# 27-JTAG_BUFFER.net
KiCad netlist of a schematic drawn in Altium Designer
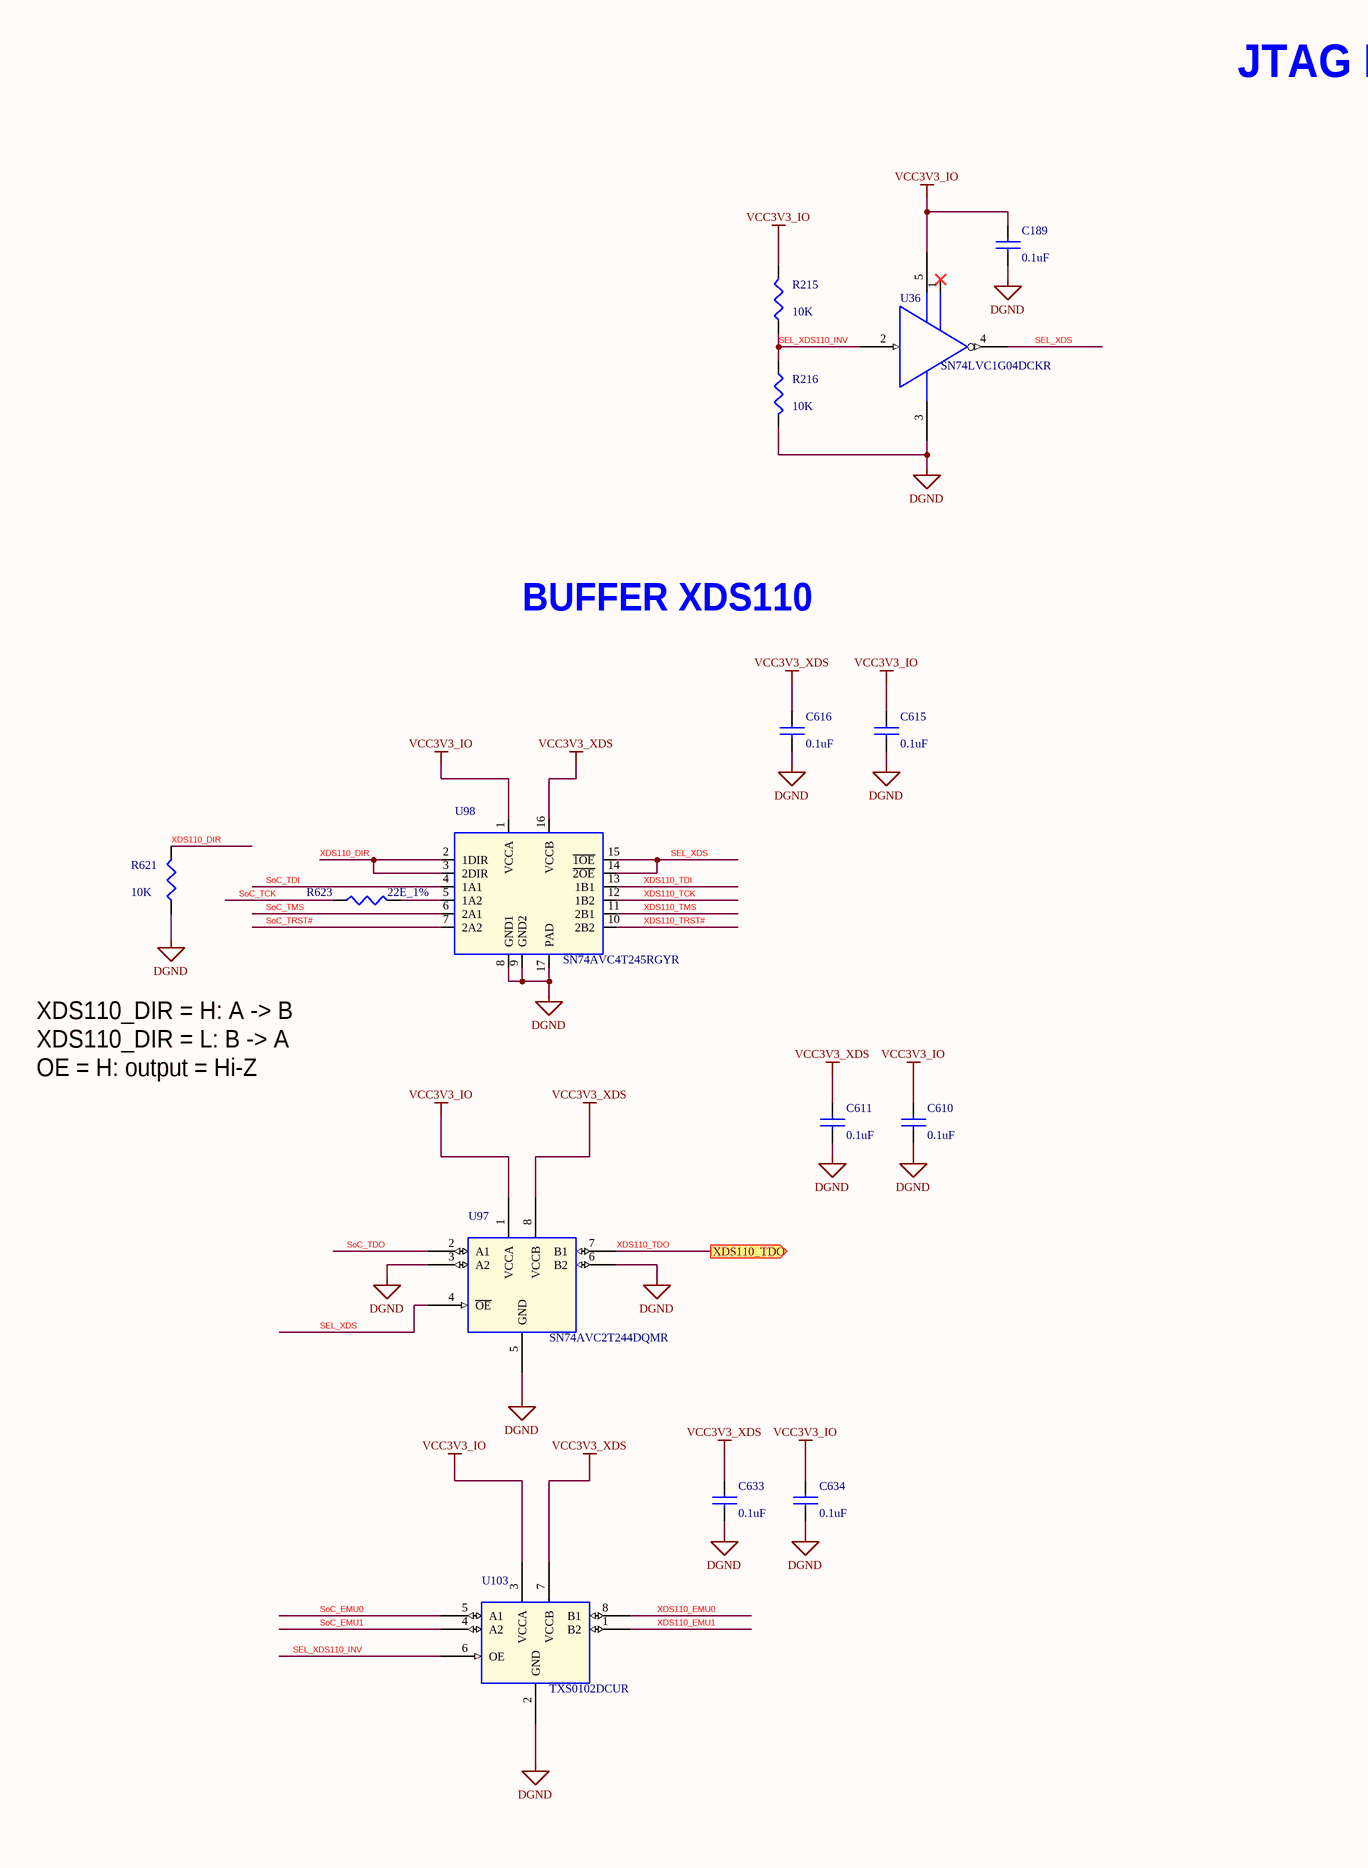
[diagram p0: 27-JTAG BUFFER.SchDoc, left]
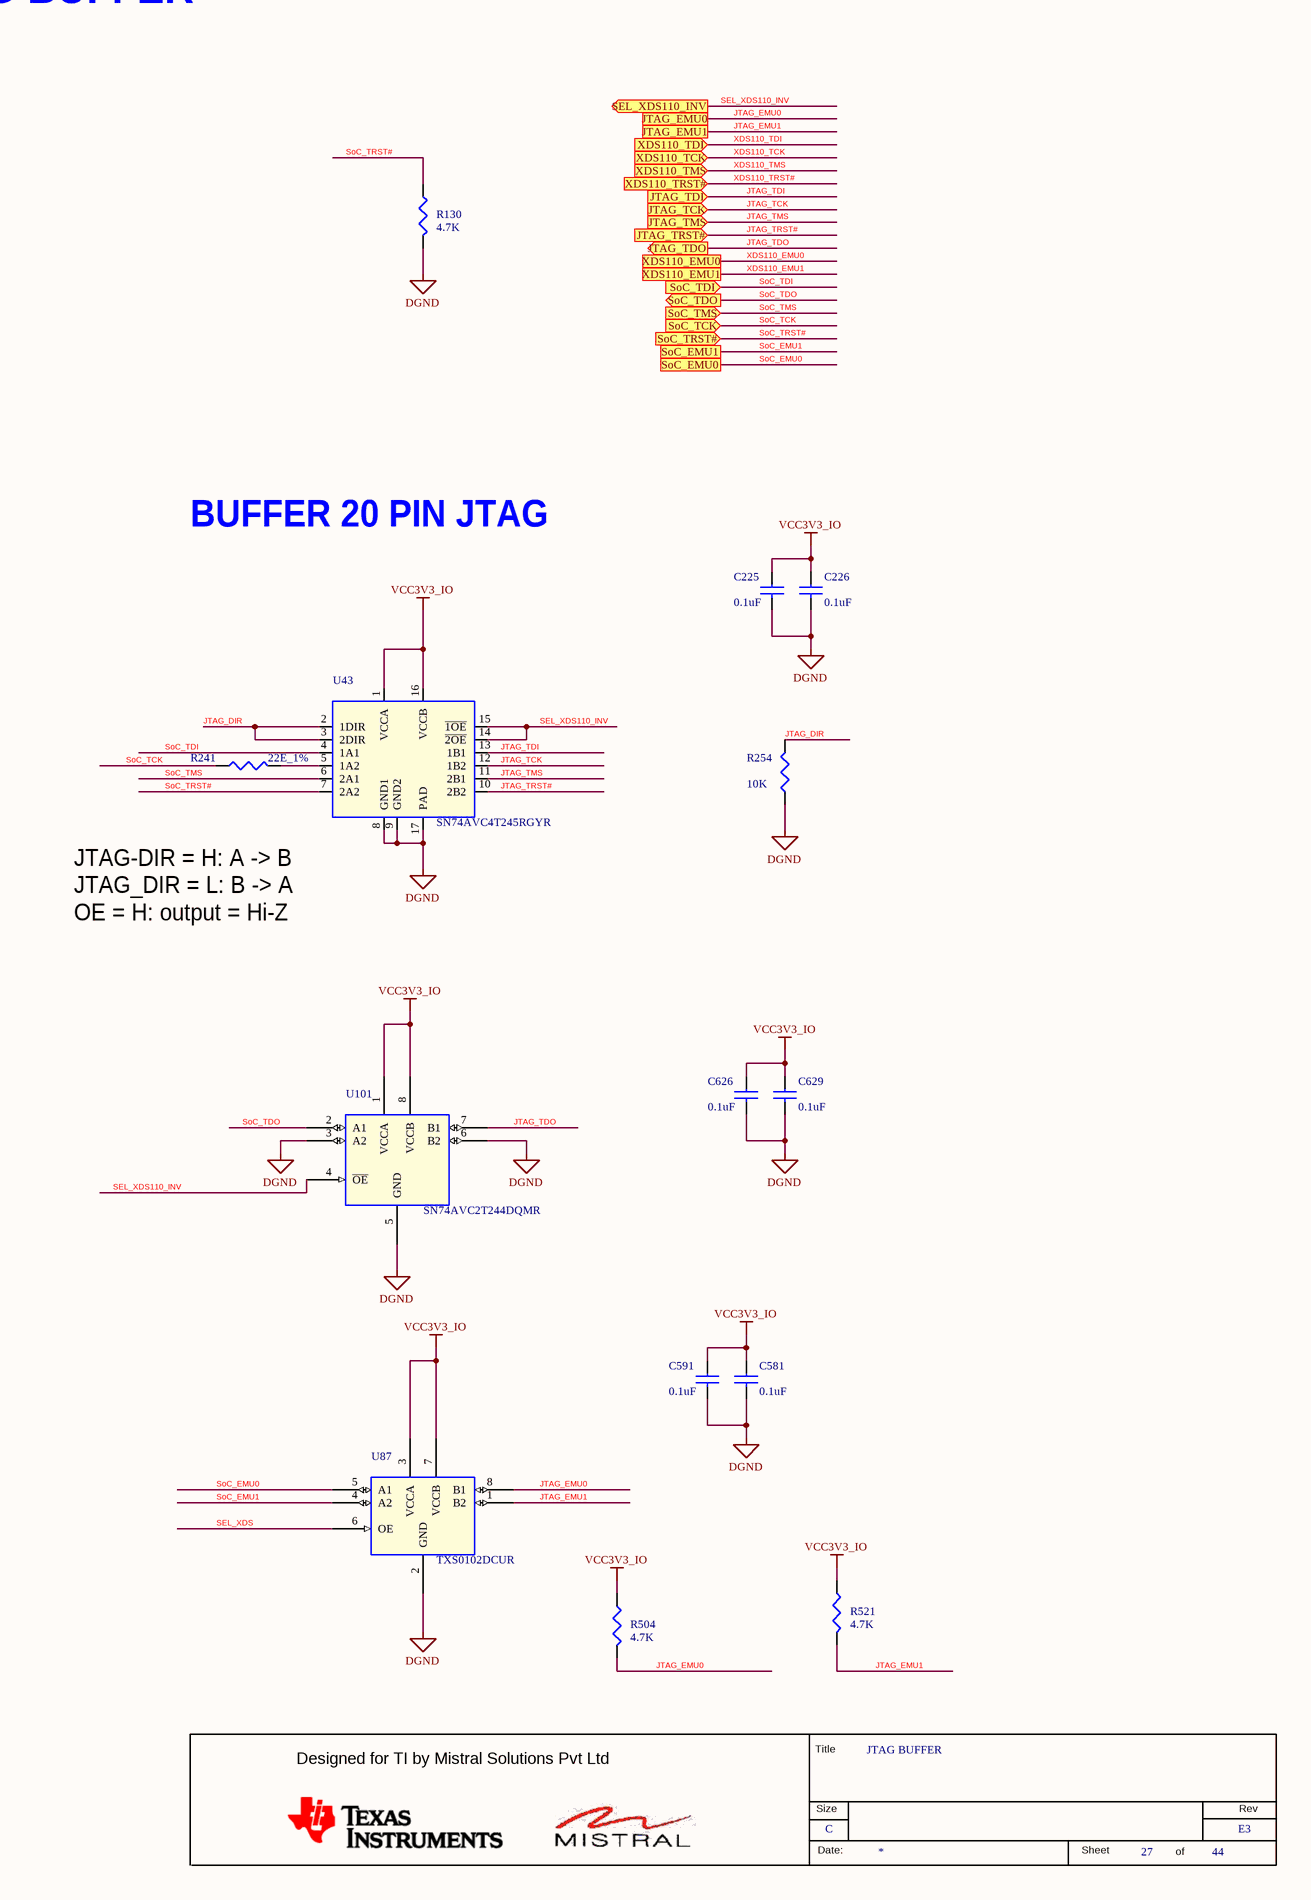
[diagram p1: 27-JTAG BUFFER.SchDoc, right]

(export (version "E")
  (design (tool "Eeschema 10.0.6"))
  (components
    (comp (ref "C189")
      (value "0.1uF")
      (footprint "CAP0201_0-5")
      (description "CAP CERAMIC 0.1uF 16V 10% X5R 0201")
      (fields (field (name "DISTRIBUTOR_PART_NUMBER") "490-16742-1-ND") (field (name "VOLTAGE") "16V"))
      (libsource (lib "*") (part "CAP_Dup5"))
    )
    (comp (ref "C225")
      (value "0.1uF")
      (footprint "CAP0201_0-5")
      (description "CAP CERAMIC 0.1uF 16V 10% X5R 0201")
      (fields
        (field (name "MISTRAL PART NO") "120009030072-R")
        (field (name "MFR_PART_NUMBER") "GRM033R61C104KE84J")
      )
      (libsource (lib "*") (part "CAP_Dup5"))
    )
    (comp (ref "C226")
      (value "0.1uF")
      (footprint "CAP0201_0-5")
      (description "CAP CERAMIC 0.1uF 16V 10% X5R 0201")
      (fields (field (name "DISTRIBUTOR_PART_NUMBER") "490-16742-1-ND") (field (name "VOLTAGE") "16V"))
      (libsource (lib "*") (part "CAP_Dup5"))
    )
    (comp (ref "C581")
      (value "0.1uF")
      (footprint "CAP0201_0-5")
      (description "CAP CERAMIC 0.1uF 16V 10% X5R 0201")
      (fields (field (name "DISTRIBUTOR_PART_NUMBER") "490-16742-1-ND") (field (name "VOLTAGE") "16V"))
      (libsource (lib "*") (part "CAP_Dup5"))
    )
    (comp (ref "C591")
      (value "0.1uF")
      (footprint "CAP0201_0-5")
      (description "CAP CERAMIC 0.1uF 16V 10% X5R 0201")
      (fields
        (field (name "MISTRAL PART NO") "120009030072-R")
        (field (name "MFR_PART_NUMBER") "GRM033R61C104KE84J")
      )
      (libsource (lib "*") (part "CAP_Dup5"))
    )
    (comp (ref "C610")
      (value "0.1uF")
      (footprint "CAP0201_0-5")
      (description "CAP CERAMIC 0.1uF 16V 10% X5R 0201")
      (fields
        (field (name "MISTRAL PART NO") "120009030072-R")
        (field (name "MFR_PART_NUMBER") "GRM033R61C104KE84J")
      )
      (libsource (lib "*") (part "CAP_Dup5"))
    )
    (comp (ref "C611")
      (value "0.1uF")
      (footprint "CAP0201_0-5")
      (description "CAP CERAMIC 0.1uF 16V 10% X5R 0201")
      (fields
        (field (name "MISTRAL PART NO") "120009030072-R")
        (field (name "MFR_PART_NUMBER") "GRM033R61C104KE84J")
      )
      (libsource (lib "*") (part "CAP_Dup5"))
    )
    (comp (ref "C615")
      (value "0.1uF")
      (footprint "CAP0201_0-5")
      (description "CAP CERAMIC 0.1uF 16V 10% X5R 0201")
      (fields (field (name "DISTRIBUTOR_PART_NUMBER") "490-16742-1-ND") (field (name "VOLTAGE") "16V"))
      (libsource (lib "*") (part "CAP_Dup5"))
    )
    (comp (ref "C616")
      (value "0.1uF")
      (footprint "CAP0201_0-5")
      (description "CAP CERAMIC 0.1uF 16V 10% X5R 0201")
      (fields
        (field (name "MISTRAL PART NO") "120009030072-R")
        (field (name "MFR_PART_NUMBER") "GRM033R61C104KE84J")
      )
      (libsource (lib "*") (part "CAP_Dup5"))
    )
    (comp (ref "C626")
      (value "0.1uF")
      (footprint "CAP0201_0-5")
      (description "CAP CERAMIC 0.1uF 16V 10% X5R 0201")
      (fields
        (field (name "MISTRAL PART NO") "120009030072-R")
        (field (name "MFR_PART_NUMBER") "GRM033R61C104KE84J")
      )
      (libsource (lib "*") (part "CAP_Dup5"))
    )
    (comp (ref "C629")
      (value "0.1uF")
      (footprint "CAP0201_0-5")
      (description "CAP CERAMIC 0.1uF 16V 10% X5R 0201")
      (fields (field (name "DISTRIBUTOR_PART_NUMBER") "490-16742-1-ND") (field (name "VOLTAGE") "16V"))
      (libsource (lib "*") (part "CAP_Dup5"))
    )
    (comp (ref "C633")
      (value "0.1uF")
      (footprint "CAP0201_0-5")
      (description "CAP CERAMIC 0.1uF 16V 10% X5R 0201")
      (fields
        (field (name "MISTRAL PART NO") "120009030072-R")
        (field (name "MFR_PART_NUMBER") "GRM033R61C104KE84J")
      )
      (libsource (lib "*") (part "CAP_Dup5"))
    )
    (comp (ref "C634")
      (value "0.1uF")
      (footprint "CAP0201_0-5")
      (description "CAP CERAMIC 0.1uF 16V 10% X5R 0201")
      (fields
        (field (name "MISTRAL PART NO") "120009030072-R")
        (field (name "MFR_PART_NUMBER") "GRM033R61C104KE84J")
      )
      (libsource (lib "*") (part "CAP_Dup5"))
    )
    (comp (ref "R130")
      (value "4.7K")
      (footprint "RES0402")
      (description "RES 4.7K 1/16W 5% 0402")
      (fields (field (name "DISTRIBUTOR_PART_NUMBER") "311-4.7KJRCT-ND") (field (name "VOLTAGE") "NA"))
      (libsource (lib "*") (part "RESISTOR_Dup3"))
    )
    (comp (ref "R215")
      (value "10K")
      (footprint "RES0402_0-5")
      (description "RES 10K 1/16W 5% 0402")
      (fields
        (field (name "MISTRAL PART NO") "110009030208-R")
        (field (name "MFR_PART_NUMBER") "RC0402JR-0710KL")
      )
      (libsource (lib "*") (part "RESISTOR_Dup5"))
    )
    (comp (ref "R216")
      (value "10K")
      (footprint "RES0402_0-5")
      (description "RES 10K 1/16W 5% 0402")
      (fields
        (field (name "MISTRAL PART NO") "110009030208-R")
        (field (name "MFR_PART_NUMBER") "RC0402JR-0710KL")
      )
      (libsource (lib "*") (part "RESISTOR_Dup5"))
    )
    (comp (ref "R241")
      (value "22E_1%")
      (footprint "RES0402")
      (description "RES 22E 1/16W 1% 0402")
      (fields
        (field (name "MISTRAL PART NO") "110009090004-P")
        (field (name "MFR_PART_NUMBER") "RC0402FR-0722RL")
      )
      (libsource (lib "*") (part "RESISTOR_Dup4"))
    )
    (comp (ref "R254")
      (value "10K")
      (footprint "RES0402_0-5")
      (description "RES 10K 1/16W 5% 0402")
      (fields
        (field (name "MISTRAL PART NO") "110009030208-R")
        (field (name "MFR_PART_NUMBER") "RC0402JR-0710KL")
      )
      (libsource (lib "*") (part "RESISTOR_Dup5"))
    )
    (comp (ref "R504")
      (value "4.7K")
      (footprint "RES0402")
      (description "RES 4.7K 1/16W 5% 0402")
      (fields (field (name "DISTRIBUTOR_PART_NUMBER") "311-4.7KJRCT-ND") (field (name "VOLTAGE") "NA"))
      (libsource (lib "*") (part "RESISTOR_Dup3"))
    )
    (comp (ref "R521")
      (value "4.7K")
      (footprint "RES0402")
      (description "RES 4.7K 1/16W 5% 0402")
      (fields (field (name "DISTRIBUTOR_PART_NUMBER") "311-4.7KJRCT-ND") (field (name "VOLTAGE") "NA"))
      (libsource (lib "*") (part "RESISTOR_Dup3"))
    )
    (comp (ref "R621")
      (value "10K")
      (footprint "RES0402_0-5")
      (description "RES 10K 1/16W 5% 0402")
      (fields
        (field (name "MISTRAL PART NO") "110009030208-R")
        (field (name "MFR_PART_NUMBER") "RC0402JR-0710KL")
      )
      (libsource (lib "*") (part "RESISTOR_Dup5"))
    )
    (comp (ref "R623")
      (value "22E_1%")
      (footprint "RES0402")
      (description "RES 22E 1/16W 1% 0402")
      (fields
        (field (name "CUST_PART_NUMBER") "4700-80047E")
        (field (name "DISTRIBUTOR_PART_NUMBER") "311-22.0LRCT-ND")
      )
      (libsource (lib "*") (part "RESISTOR_Dup4"))
    )
    (comp (ref "U36")
      (value "SN74LVC1G04DCKR")
      (footprint "SC70-5")
      (description "IC SINGLE INVERTER GATE SC70-5")
      (fields
        (field (name "MISTRAL PART NO") "141009070007-R")
        (field (name "DISTRIBUTOR_PART_NUMBER") "296-11600-1-ND")
      )
      (libsource (lib "*") (part "SN74LVC1G04DCKR_SC70-5"))
    )
    (comp (ref "U43")
      (value "SN74AVC4T245RGYR")
      (footprint "QFN16_19-68_160X140")
      (description "IC 4-BIT DUAL SUPPLY BUS TRANSCEIVER QFN16")
      (fields
        (field (name "DISTRIBUTOR_PART_NUMBER") "296-18231-1-ND")
        (field (name "MISTRAL PART NO") "141009030112-R")
      )
      (libsource (lib "*") (part "SN74AVC4T245RGYR_QFN16"))
    )
    (comp (ref "U87")
      (value "TXS0102DCUR")
      (footprint "VSSOP8_19-68_85X95_0-9")
      (description "IC 2BIT BI-DIR VOLTAGE-LEVEL TRANSLATOR US8(VSSOP8)")
      (fields
        (field (name "DISTRIBUTOR_PART_NUMBER") "296-21931-1-ND")
        (field (name "VOLTAGE") "NA")
        (field (name "LIBRARY PATH") "Y~{:}MIS_DATABAS~{E}Librar~{y}ALTIUM_TOO~{L}SCHEMATICS_PART~{S}MS_MISCINTERFACE_Library.schlib")
      )
      (libsource (lib "*") (part "TXS0102DCUR_VSSOP8"))
    )
    (comp (ref "U97")
      (value "SN74AVC2T244DQMR")
      (footprint "X2SON8_15-74_70X50")
      (description "IC 2-BIT UNDIRECTIONAL VOLTAGE-LEVEL TRANSLATOR X2SON8")
      (fields (field (name "MISTRAL PART NO") "141016030002-R") (field (name "TOLERANCE") "NA"))
      (libsource (lib "*") (part "SN74AVC2T244DQMR_X2SON8"))
    )
    (comp (ref "U98")
      (value "SN74AVC4T245RGYR")
      (footprint "QFN16_19-68_160X140")
      (description "IC 4-BIT DUAL SUPPLY BUS TRANSCEIVER QFN16")
      (fields
        (field (name "MISTRAL PART NO") "141009030112-R")
        (field (name "DISTRIBUTOR_PART_NUMBER") "296-18231-1-ND")
      )
      (libsource (lib "*") (part "SN74AVC4T245RGYR_QFN16"))
    )
    (comp (ref "U101")
      (value "SN74AVC2T244DQMR")
      (footprint "X2SON8_15-74_70X50")
      (description "IC 2-BIT UNDIRECTIONAL VOLTAGE-LEVEL TRANSLATOR X2SON8")
      (fields (field (name "MISTRAL PART NO") "141016030002-R") (field (name "TOLERANCE") "NA"))
      (libsource (lib "*") (part "SN74AVC2T244DQMR_X2SON8"))
    )
    (comp (ref "U103")
      (value "TXS0102DCUR")
      (footprint "VSSOP8_19-68_85X95_0-9")
      (description "IC 2BIT BI-DIR VOLTAGE-LEVEL TRANSLATOR US8(VSSOP8)")
      (fields
        (field (name "MISTRAL PART NO") "141009030376-R")
        (field (name "TOLERANCE") "NA")
        (field (name "LIBRARY PATH") "Y~{:}MIS_DATABAS~{E}Librar~{y}ALTIUM_TOO~{L}SCHEMATICS_PART~{S}MS_MISCINTERFACE_Library.schlib")
      )
      (libsource (lib "*") (part "TXS0102DCUR_VSSOP8"))
    )
  )
  (nets
    (net (code "1") (name "/JTAG_DIR") (class "Default")
      (node (ref "R254") (pin "2") (pinfunction "2_2") (pintype "passive"))
      (node (ref "U43") (pin "2") (pinfunction "1DIR_2") (pintype "passive"))
      (node (ref "U43") (pin "3") (pinfunction "2DIR_3") (pintype "passive"))
    )
    (net (code "2") (name "/JTAG_EMU0") (class "Default")
      (node (ref "R504") (pin "2") (pinfunction "2_2") (pintype "passive"))
      (node (ref "U87") (pin "8") (pinfunction "B1_8") (pintype "bidirectional"))
    )
    (net (code "3") (name "/JTAG_EMU1") (class "Default")
      (node (ref "R521") (pin "2") (pinfunction "2_2") (pintype "passive"))
      (node (ref "U87") (pin "1") (pinfunction "B2_1") (pintype "bidirectional"))
    )
    (net (code "4") (name "/JTAG_TCK") (class "Default")
      (node (ref "U43") (pin "12") (pinfunction "1B2_12") (pintype "bidirectional"))
    )
    (net (code "5") (name "/JTAG_TDI") (class "Default")
      (node (ref "U43") (pin "13") (pinfunction "1B1_13") (pintype "bidirectional"))
    )
    (net (code "6") (name "/JTAG_TDO") (class "Default")
      (node (ref "U101") (pin "7") (pinfunction "B1_7") (pintype "bidirectional"))
    )
    (net (code "7") (name "/JTAG_TMS") (class "Default")
      (node (ref "U43") (pin "11") (pinfunction "2B1_11") (pintype "bidirectional"))
    )
    (net (code "8") (name "/JTAG_TRST#") (class "Default")
      (node (ref "U43") (pin "10") (pinfunction "2B2_10") (pintype "bidirectional"))
    )
    (net (code "9") (name "/SEL_XDS") (class "Default")
      (node (ref "U36") (pin "4") (pinfunction "Y_4") (pintype "output"))
      (node (ref "U87") (pin "6") (pinfunction "OE_6") (pintype "input"))
      (node (ref "U97") (pin "4") (pinfunction "~{OE}_4") (pintype "input"))
      (node (ref "U98") (pin "14") (pinfunction "~{2OE}_14") (pintype "passive"))
      (node (ref "U98") (pin "15") (pinfunction "~{1OE}_15") (pintype "passive"))
    )
    (net (code "10") (name "/SEL_XDS110_INV") (class "Default")
      (node (ref "R215") (pin "1") (pinfunction "1_1") (pintype "passive"))
      (node (ref "R216") (pin "1") (pinfunction "1_1") (pintype "passive"))
      (node (ref "U101") (pin "4") (pinfunction "~{OE}_4") (pintype "input"))
      (node (ref "U103") (pin "6") (pinfunction "OE_6") (pintype "input"))
      (node (ref "U36") (pin "2") (pinfunction "A_2") (pintype "input"))
      (node (ref "U43") (pin "14") (pinfunction "~{2OE}_14") (pintype "passive"))
      (node (ref "U43") (pin "15") (pinfunction "~{1OE}_15") (pintype "passive"))
    )
    (net (code "11") (name "/SoC_EMU0") (class "Default")
      (node (ref "U103") (pin "5") (pinfunction "A1_5") (pintype "bidirectional"))
      (node (ref "U87") (pin "5") (pinfunction "A1_5") (pintype "bidirectional"))
    )
    (net (code "12") (name "/SoC_EMU1") (class "Default")
      (node (ref "U103") (pin "4") (pinfunction "A2_4") (pintype "bidirectional"))
      (node (ref "U87") (pin "4") (pinfunction "A2_4") (pintype "bidirectional"))
    )
    (net (code "13") (name "/SoC_TCK") (class "Default")
      (node (ref "R241") (pin "2") (pinfunction "2_2") (pintype "passive"))
      (node (ref "R623") (pin "2") (pinfunction "2_2") (pintype "passive"))
    )
    (net (code "14") (name "/SoC_TDI") (class "Default")
      (node (ref "U43") (pin "4") (pinfunction "1A1_4") (pintype "bidirectional"))
      (node (ref "U98") (pin "4") (pinfunction "1A1_4") (pintype "bidirectional"))
    )
    (net (code "15") (name "/SoC_TDO") (class "Default")
      (node (ref "U101") (pin "2") (pinfunction "A1_2") (pintype "bidirectional"))
      (node (ref "U97") (pin "2") (pinfunction "A1_2") (pintype "bidirectional"))
    )
    (net (code "16") (name "/SoC_TMS") (class "Default")
      (node (ref "U43") (pin "6") (pinfunction "2A1_6") (pintype "bidirectional"))
      (node (ref "U98") (pin "6") (pinfunction "2A1_6") (pintype "bidirectional"))
    )
    (net (code "17") (name "/SoC_TRST#") (class "Default")
      (node (ref "R130") (pin "1") (pinfunction "1_1") (pintype "passive"))
      (node (ref "U43") (pin "7") (pinfunction "2A2_7") (pintype "bidirectional"))
      (node (ref "U98") (pin "7") (pinfunction "2A2_7") (pintype "bidirectional"))
    )
    (net (code "18") (name "/XDS110_DIR") (class "Default")
      (node (ref "R621") (pin "2") (pinfunction "2_2") (pintype "passive"))
      (node (ref "U98") (pin "2") (pinfunction "1DIR_2") (pintype "passive"))
      (node (ref "U98") (pin "3") (pinfunction "2DIR_3") (pintype "passive"))
    )
    (net (code "19") (name "/XDS110_EMU0") (class "Default")
      (node (ref "U103") (pin "8") (pinfunction "B1_8") (pintype "bidirectional"))
    )
    (net (code "20") (name "/XDS110_EMU1") (class "Default")
      (node (ref "U103") (pin "1") (pinfunction "B2_1") (pintype "bidirectional"))
    )
    (net (code "21") (name "/XDS110_TCK") (class "Default")
      (node (ref "U98") (pin "12") (pinfunction "1B2_12") (pintype "bidirectional"))
    )
    (net (code "22") (name "/XDS110_TDI") (class "Default")
      (node (ref "U98") (pin "13") (pinfunction "1B1_13") (pintype "bidirectional"))
    )
    (net (code "23") (name "/XDS110_TDO") (class "Default")
      (node (ref "U97") (pin "7") (pinfunction "B1_7") (pintype "bidirectional"))
    )
    (net (code "24") (name "/XDS110_TMS") (class "Default")
      (node (ref "U98") (pin "11") (pinfunction "2B1_11") (pintype "bidirectional"))
    )
    (net (code "25") (name "/XDS110_TRST#") (class "Default")
      (node (ref "U98") (pin "10") (pinfunction "2B2_10") (pintype "bidirectional"))
    )
    (net (code "26") (name "DGND") (class "Default")
      (node (ref "C189") (pin "2") (pinfunction "2_2") (pintype "passive"))
      (node (ref "C225") (pin "2") (pinfunction "2_2") (pintype "passive"))
      (node (ref "C226") (pin "2") (pinfunction "2_2") (pintype "passive"))
      (node (ref "C581") (pin "2") (pinfunction "2_2") (pintype "passive"))
      (node (ref "C591") (pin "2") (pinfunction "2_2") (pintype "passive"))
      (node (ref "C610") (pin "2") (pinfunction "2_2") (pintype "passive"))
      (node (ref "C611") (pin "2") (pinfunction "2_2") (pintype "passive"))
      (node (ref "C615") (pin "2") (pinfunction "2_2") (pintype "passive"))
      (node (ref "C616") (pin "2") (pinfunction "2_2") (pintype "passive"))
      (node (ref "C626") (pin "2") (pinfunction "2_2") (pintype "passive"))
      (node (ref "C629") (pin "2") (pinfunction "2_2") (pintype "passive"))
      (node (ref "C633") (pin "2") (pinfunction "2_2") (pintype "passive"))
      (node (ref "C634") (pin "2") (pinfunction "2_2") (pintype "passive"))
      (node (ref "R130") (pin "2") (pinfunction "2_2") (pintype "passive"))
      (node (ref "R216") (pin "2") (pinfunction "2_2") (pintype "passive"))
      (node (ref "R254") (pin "1") (pinfunction "1_1") (pintype "passive"))
      (node (ref "R621") (pin "1") (pinfunction "1_1") (pintype "passive"))
      (node (ref "U101") (pin "3") (pinfunction "A2_3") (pintype "bidirectional"))
      (node (ref "U101") (pin "5") (pinfunction "GND_5") (pintype "power_in"))
      (node (ref "U101") (pin "6") (pinfunction "B2_6") (pintype "bidirectional"))
      (node (ref "U103") (pin "2") (pinfunction "GND_2") (pintype "power_in"))
      (node (ref "U36") (pin "3") (pinfunction "GND_3") (pintype "power_in"))
      (node (ref "U43") (pin "17") (pinfunction "PAD_17") (pintype "power_in"))
      (node (ref "U43") (pin "8") (pinfunction "GND1_8") (pintype "power_in"))
      (node (ref "U43") (pin "9") (pinfunction "GND2_9") (pintype "power_in"))
      (node (ref "U87") (pin "2") (pinfunction "GND_2") (pintype "power_in"))
      (node (ref "U97") (pin "3") (pinfunction "A2_3") (pintype "bidirectional"))
      (node (ref "U97") (pin "5") (pinfunction "GND_5") (pintype "power_in"))
      (node (ref "U97") (pin "6") (pinfunction "B2_6") (pintype "bidirectional"))
      (node (ref "U98") (pin "17") (pinfunction "PAD_17") (pintype "power_in"))
      (node (ref "U98") (pin "8") (pinfunction "GND1_8") (pintype "power_in"))
      (node (ref "U98") (pin "9") (pinfunction "GND2_9") (pintype "power_in"))
    )
    (net (code "27") (name "Net-(U43-1A2)") (class "Default")
      (node (ref "R241") (pin "1") (pinfunction "1_1") (pintype "passive"))
      (node (ref "U43") (pin "5") (pinfunction "1A2_5") (pintype "bidirectional"))
    )
    (net (code "28") (name "Net-(U98-1A2)") (class "Default")
      (node (ref "R623") (pin "1") (pinfunction "1_1") (pintype "passive"))
      (node (ref "U98") (pin "5") (pinfunction "1A2_5") (pintype "bidirectional"))
    )
    (net (code "29") (name "VCC3V3_IO") (class "Default")
      (node (ref "C189") (pin "1") (pinfunction "1_1") (pintype "passive"))
      (node (ref "C225") (pin "1") (pinfunction "1_1") (pintype "passive"))
      (node (ref "C226") (pin "1") (pinfunction "1_1") (pintype "passive"))
      (node (ref "C581") (pin "1") (pinfunction "1_1") (pintype "passive"))
      (node (ref "C591") (pin "1") (pinfunction "1_1") (pintype "passive"))
      (node (ref "C610") (pin "1") (pinfunction "1_1") (pintype "passive"))
      (node (ref "C615") (pin "1") (pinfunction "1_1") (pintype "passive"))
      (node (ref "C626") (pin "1") (pinfunction "1_1") (pintype "passive"))
      (node (ref "C629") (pin "1") (pinfunction "1_1") (pintype "passive"))
      (node (ref "C634") (pin "1") (pinfunction "1_1") (pintype "passive"))
      (node (ref "R215") (pin "2") (pinfunction "2_2") (pintype "passive"))
      (node (ref "R504") (pin "1") (pinfunction "1_1") (pintype "passive"))
      (node (ref "R521") (pin "1") (pinfunction "1_1") (pintype "passive"))
      (node (ref "U101") (pin "1") (pinfunction "VCCA_1") (pintype "power_in"))
      (node (ref "U101") (pin "8") (pinfunction "VCCB_8") (pintype "power_in"))
      (node (ref "U103") (pin "3") (pinfunction "VCCA_3") (pintype "power_in"))
      (node (ref "U36") (pin "5") (pinfunction "VCC_5") (pintype "power_in"))
      (node (ref "U43") (pin "1") (pinfunction "VCCA_1") (pintype "power_in"))
      (node (ref "U43") (pin "16") (pinfunction "VCCB_16") (pintype "power_in"))
      (node (ref "U87") (pin "3") (pinfunction "VCCA_3") (pintype "power_in"))
      (node (ref "U87") (pin "7") (pinfunction "VCCB_7") (pintype "power_in"))
      (node (ref "U97") (pin "1") (pinfunction "VCCA_1") (pintype "power_in"))
      (node (ref "U98") (pin "1") (pinfunction "VCCA_1") (pintype "power_in"))
    )
    (net (code "30") (name "VCC3V3_XDS") (class "Default")
      (node (ref "C611") (pin "1") (pinfunction "1_1") (pintype "passive"))
      (node (ref "C616") (pin "1") (pinfunction "1_1") (pintype "passive"))
      (node (ref "C633") (pin "1") (pinfunction "1_1") (pintype "passive"))
      (node (ref "U103") (pin "7") (pinfunction "VCCB_7") (pintype "power_in"))
      (node (ref "U97") (pin "8") (pinfunction "VCCB_8") (pintype "power_in"))
      (node (ref "U98") (pin "16") (pinfunction "VCCB_16") (pintype "power_in"))
    )
    (net (code "31") (name "unconnected-(U36-NC-Pad1)") (class "Default")
      (node (ref "U36") (pin "1") (pinfunction "NC_1") (pintype "passive+no_connect"))
    )
  )
)
